# finalproject_2.net
KiCad netlist of a schematic drawn in EAGLE
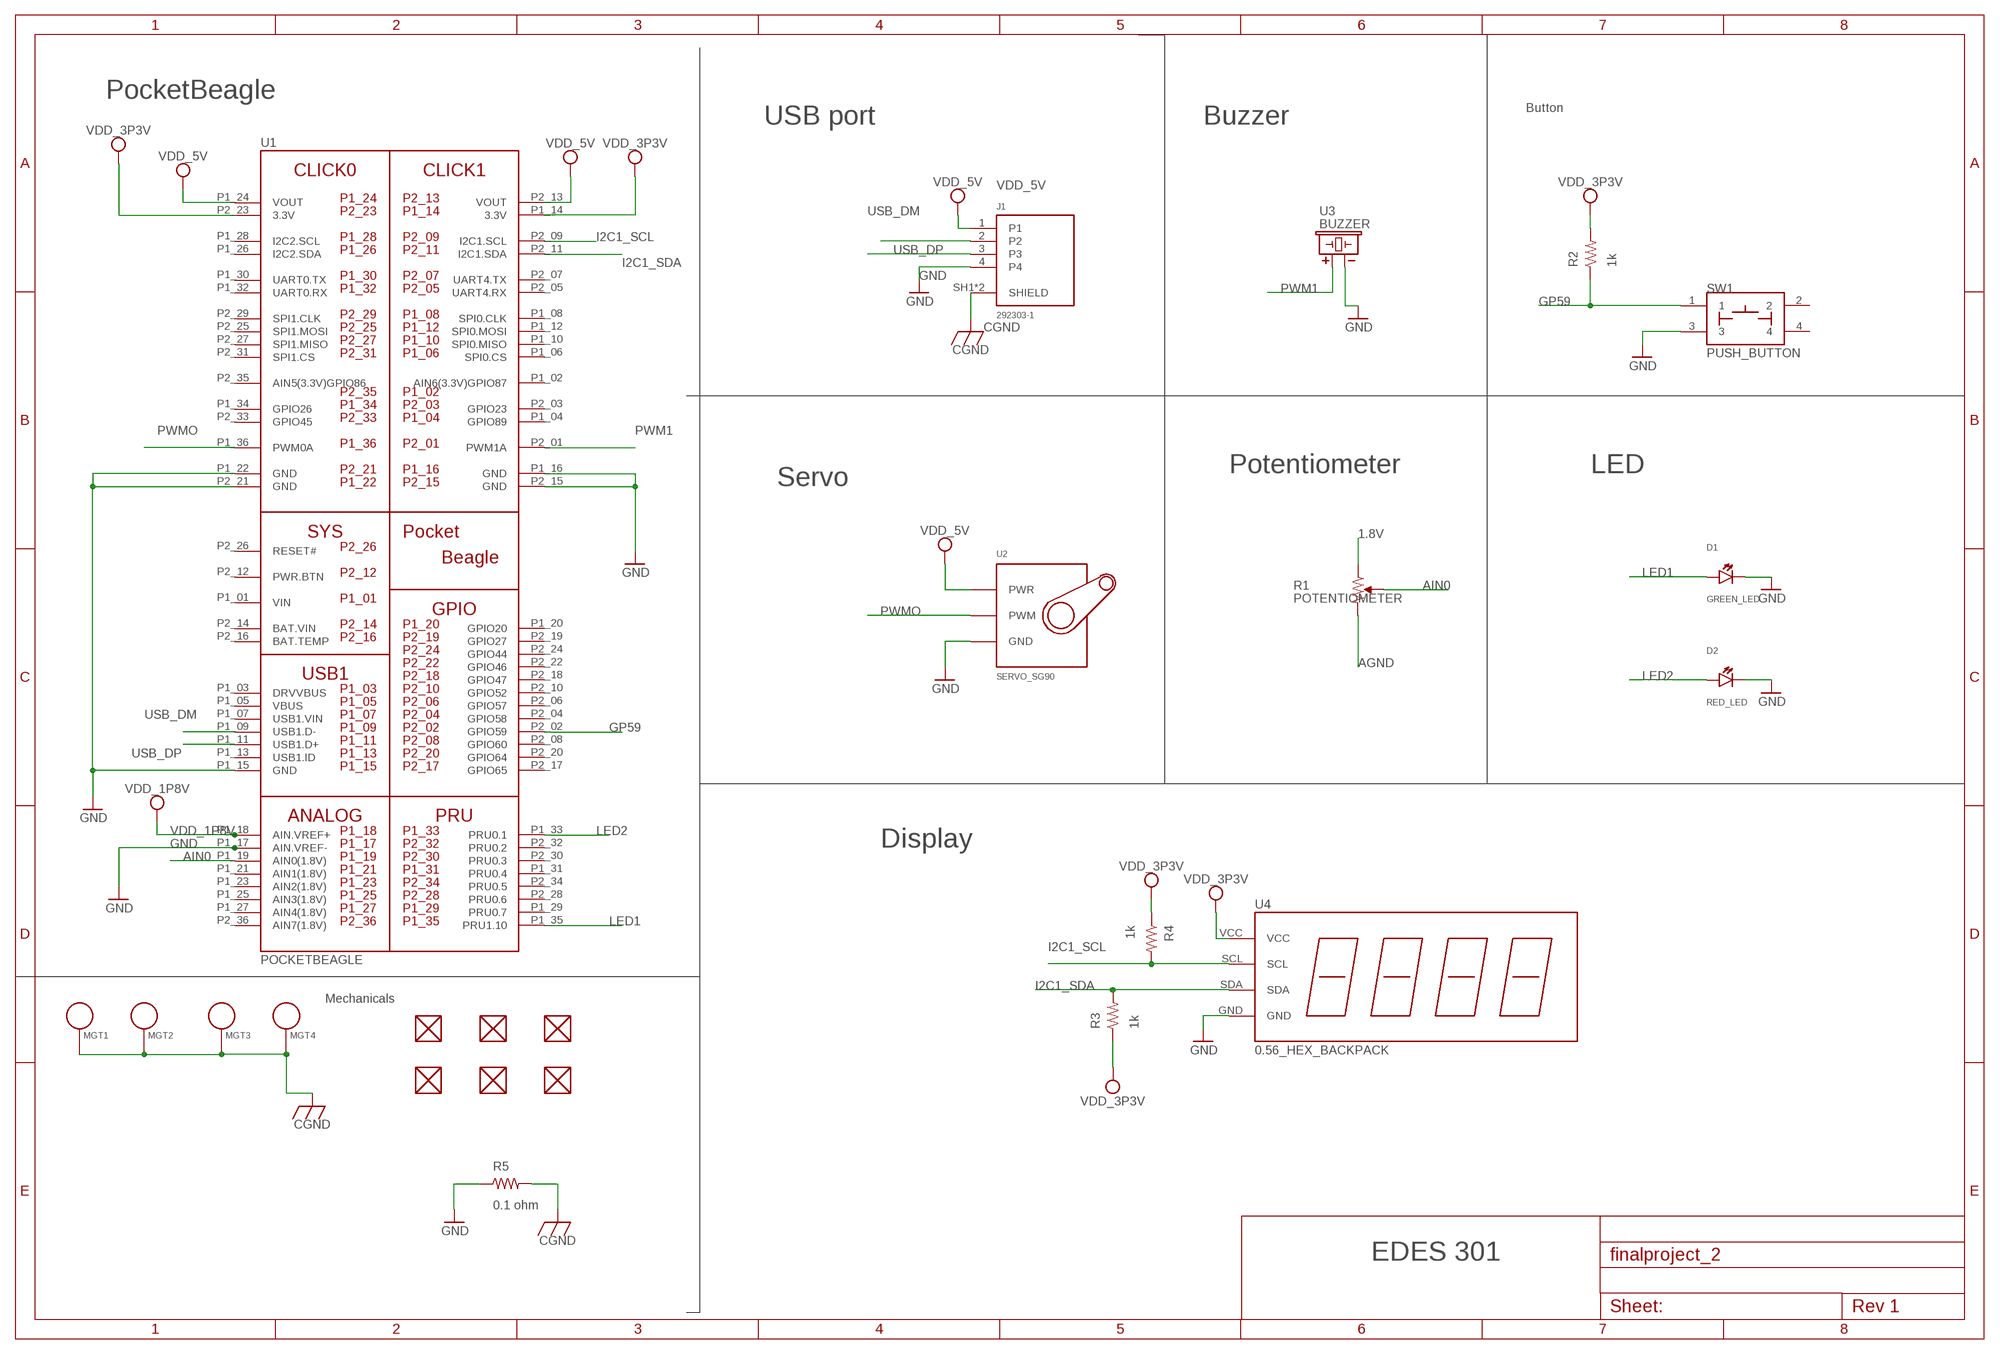
[diagram p0: schematic, sheet 1]

(export (version "E")
  (design (tool "Eeschema 10.0.6"))
  (components
    (comp (ref "D1")
      (value "GREEN_LED")
      (footprint "eagle-import:EIA-STD")
      (libsource (lib "eagle-import") (part "LED"))
    )
    (comp (ref "D2")
      (value "RED_LED")
      (footprint "eagle-import:EIA-STD")
      (libsource (lib "eagle-import") (part "LED"))
    )
    (comp (ref "FUD1")
      (value "FIDUCIAL")
      (footprint "eagle-import:FIDUCIAL_40MIL")
      (libsource (lib "eagle-import") (part "FIDUCIAL"))
    )
    (comp (ref "FUD2")
      (value "FIDUCIAL")
      (footprint "eagle-import:FIDUCIAL_40MIL")
      (libsource (lib "eagle-import") (part "FIDUCIAL"))
    )
    (comp (ref "FUD3")
      (value "FIDUCIAL")
      (footprint "eagle-import:FIDUCIAL_40MIL")
      (libsource (lib "eagle-import") (part "FIDUCIAL"))
    )
    (comp (ref "FUD4")
      (value "FIDUCIAL")
      (footprint "eagle-import:FIDUCIAL_40MIL")
      (libsource (lib "eagle-import") (part "FIDUCIAL"))
    )
    (comp (ref "FUD5")
      (value "FIDUCIAL")
      (footprint "eagle-import:FIDUCIAL_40MIL")
      (libsource (lib "eagle-import") (part "FIDUCIAL"))
    )
    (comp (ref "FUD6")
      (value "FIDUCIAL")
      (footprint "eagle-import:FIDUCIAL_40MIL")
      (libsource (lib "eagle-import") (part "FIDUCIAL"))
    )
    (comp (ref "J1")
      (value "292303-1")
      (footprint "eagle-import:TE_292303-1")
      (fields (field (name "MF") "TE Connectivity"))
      (libsource (lib "eagle-import") (part "292303-1"))
    )
    (comp (ref "MGT1")
      (value "MOUNTING_HOLE")
      (footprint "eagle-import:MOUNTING_HOLE")
      (libsource (lib "eagle-import") (part "MOUNTING_HOLE"))
    )
    (comp (ref "MGT2")
      (value "MOUNTING_HOLE")
      (footprint "eagle-import:MOUNTING_HOLE")
      (libsource (lib "eagle-import") (part "MOUNTING_HOLE"))
    )
    (comp (ref "MGT3")
      (value "MOUNTING_HOLE")
      (footprint "eagle-import:MOUNTING_HOLE")
      (libsource (lib "eagle-import") (part "MOUNTING_HOLE"))
    )
    (comp (ref "MGT4")
      (value "MOUNTING_HOLE")
      (footprint "eagle-import:MOUNTING_HOLE")
      (libsource (lib "eagle-import") (part "MOUNTING_HOLE"))
    )
    (comp (ref "R1")
      (value "POTENTIOMETER")
      (footprint "eagle-import:POT-PO90S")
      (libsource (lib "eagle-import") (part "POTENTIOMETER"))
    )
    (comp (ref "R2")
      (value "1k")
      (footprint "eagle-import:R0402")
      (libsource (lib "eagle-import") (part "R_R0402"))
    )
    (comp (ref "R3")
      (value "1k")
      (footprint "eagle-import:R0402")
      (libsource (lib "eagle-import") (part "R_R0402"))
    )
    (comp (ref "R4")
      (value "1k")
      (footprint "eagle-import:R0402")
      (libsource (lib "eagle-import") (part "R_R0402"))
    )
    (comp (ref "R5")
      (value "0.1 ohm")
      (footprint "eagle-import:R0805")
      (libsource (lib "eagle-import") (part "R_R0805"))
    )
    (comp (ref "SW1")
      (value "PUSH_BUTTON")
      (footprint "eagle-import:BUTTON_12.5MM")
      (libsource (lib "eagle-import") (part "PUSH_BUTTON"))
    )
    (comp (ref "U1")
      (value "POCKETBEAGLE")
      (footprint "eagle-import:POCKETBEAGLE")
      (libsource (lib "eagle-import") (part "POCKETBEAGLE"))
    )
    (comp (ref "U2")
      (value "SERVO_SG90")
      (footprint "eagle-import:SERVO-X1")
      (libsource (lib "eagle-import") (part "SERVO_SG90"))
    )
    (comp (ref "U3")
      (value "BUZZER")
      (footprint "eagle-import:BUZZER_6.5MM")
      (libsource (lib "eagle-import") (part "BUZZER"))
    )
    (comp (ref "U4")
      (value "0.56_HEX_BACKPACK")
      (footprint "eagle-import:0.56_HEX_BACKPACK")
      (libsource (lib "eagle-import") (part "0.56_HEX_BACKPACK"))
    )
  )
  (nets
    (net (code "1") (name "/1.8V") (class "Default")
      (node (ref "R1") (pin "CCW") (pinfunction "CCW_CCW") (pintype "passive"))
    )
    (net (code "2") (name "/AGND") (class "Default")
      (node (ref "R1") (pin "CW") (pinfunction "CW_CW") (pintype "passive"))
    )
    (net (code "3") (name "/AIN0") (class "Default")
      (node (ref "R1") (pin "S") (pinfunction "S_S") (pintype "bidirectional"))
      (node (ref "U1") (pin "P1_19") (pinfunction "AIN0(1.8V)_P1_19") (pintype "input"))
    )
    (net (code "4") (name "/BAT.VIN") (class "Default")
      (node (ref "U1") (pin "P2_14") (pinfunction "BAT.VIN_P2_14") (pintype "power_in"))
    )
    (net (code "5") (name "/GP59") (class "Default")
      (node (ref "R2") (pin "1") (pinfunction "1_1") (pintype "passive"))
      (node (ref "SW1") (pin "1") (pinfunction "1_1") (pintype "bidirectional"))
      (node (ref "U1") (pin "P2_02") (pinfunction "GPIO59_P2_02") (pintype "bidirectional"))
    )
    (net (code "6") (name "/I2C1_SCL") (class "Default")
      (node (ref "R4") (pin "2") (pinfunction "2_2") (pintype "passive"))
      (node (ref "U1") (pin "P2_09") (pinfunction "I2C1.SCL_P2_09") (pintype "bidirectional"))
      (node (ref "U4") (pin "SCL") (pinfunction "SCL_SCL") (pintype "bidirectional"))
    )
    (net (code "7") (name "/I2C1_SDA") (class "Default")
      (node (ref "R3") (pin "2") (pinfunction "2_2") (pintype "passive"))
      (node (ref "U1") (pin "P2_11") (pinfunction "I2C1.SDA_P2_11") (pintype "bidirectional"))
      (node (ref "U4") (pin "SDA") (pinfunction "SDA_SDA") (pintype "bidirectional"))
    )
    (net (code "8") (name "/LED1") (class "Default")
      (node (ref "D1") (pin "ANODE") (pinfunction "ANODE_ANODE") (pintype "bidirectional"))
      (node (ref "U1") (pin "P1_35") (pinfunction "PRU1.10_P1_35") (pintype "bidirectional"))
    )
    (net (code "9") (name "/LED2") (class "Default")
      (node (ref "D2") (pin "ANODE") (pinfunction "ANODE_ANODE") (pintype "bidirectional"))
      (node (ref "U1") (pin "P1_33") (pinfunction "PRU0.1_P1_33") (pintype "bidirectional"))
    )
    (net (code "10") (name "/PWM1") (class "Default")
      (node (ref "U1") (pin "P2_01") (pinfunction "PWM1A_P2_01") (pintype "bidirectional"))
      (node (ref "U3") (pin "+") (pinfunction "+_+") (pintype "passive"))
    )
    (net (code "11") (name "/PWMO") (class "Default")
      (node (ref "U1") (pin "P1_36") (pinfunction "PWM0A_P1_36") (pintype "bidirectional"))
      (node (ref "U2") (pin "SIG") (pinfunction "PWM_SIG") (pintype "bidirectional"))
    )
    (net (code "12") (name "/USB_DM") (class "Default")
      (node (ref "J1") (pin "2") (pinfunction "P2_2") (pintype "passive"))
      (node (ref "U1") (pin "P1_09") (pinfunction "USB1.D-_P1_09") (pintype "bidirectional"))
    )
    (net (code "13") (name "/USB_DP") (class "Default")
      (node (ref "J1") (pin "3") (pinfunction "P3_3") (pintype "passive"))
      (node (ref "U1") (pin "P1_11") (pinfunction "USB1.D+_P1_11") (pintype "bidirectional"))
    )
    (net (code "14") (name "/VIN") (class "Default")
      (node (ref "U1") (pin "P1_01") (pinfunction "VIN_P1_01") (pintype "power_in"))
    )
    (net (code "15") (name "CGND") (class "Default")
      (node (ref "J1") (pin "SH1") (pinfunction "SHIELD_SH1") (pintype "passive"))
      (node (ref "J1") (pin "SH2") (pinfunction "SHIELD_SH2") (pintype "passive"))
      (node (ref "MGT1") (pin "P$1") (pinfunction "P$1_P$1") (pintype "bidirectional"))
      (node (ref "MGT2") (pin "P$1") (pinfunction "P$1_P$1") (pintype "bidirectional"))
      (node (ref "MGT3") (pin "P$1") (pinfunction "P$1_P$1") (pintype "bidirectional"))
      (node (ref "MGT4") (pin "P$1") (pinfunction "P$1_P$1") (pintype "bidirectional"))
      (node (ref "R5") (pin "2") (pinfunction "2_2") (pintype "passive"))
    )
    (net (code "16") (name "GND") (class "Default")
      (node (ref "D1") (pin "CATHODE") (pinfunction "CATHODE_CATHODE") (pintype "bidirectional"))
      (node (ref "D2") (pin "CATHODE") (pinfunction "CATHODE_CATHODE") (pintype "bidirectional"))
      (node (ref "J1") (pin "4") (pinfunction "P4_4") (pintype "passive"))
      (node (ref "R5") (pin "1") (pinfunction "1_1") (pintype "passive"))
      (node (ref "SW1") (pin "3") (pinfunction "3_3") (pintype "bidirectional"))
      (node (ref "U1") (pin "P1_15") (pinfunction "GND_P1_15") (pintype "bidirectional"))
      (node (ref "U1") (pin "P1_16") (pinfunction "GND_P1_16") (pintype "power_in"))
      (node (ref "U1") (pin "P1_17") (pinfunction "AIN.VREF-_P1_17") (pintype "input"))
      (node (ref "U1") (pin "P1_22") (pinfunction "GND_P1_22") (pintype "power_in"))
      (node (ref "U1") (pin "P2_15") (pinfunction "GND_P2_15") (pintype "power_in"))
      (node (ref "U1") (pin "P2_21") (pinfunction "GND_P2_21") (pintype "power_in"))
      (node (ref "U2") (pin "GND") (pinfunction "GND_GND") (pintype "bidirectional"))
      (node (ref "U3") (pin "-") (pinfunction "-_-") (pintype "passive"))
      (node (ref "U4") (pin "GND") (pinfunction "GND_GND") (pintype "bidirectional"))
    )
    (net (code "17") (name "VDD_1P8V") (class "Default")
      (node (ref "U1") (pin "P1_18") (pinfunction "AIN.VREF+_P1_18") (pintype "input"))
    )
    (net (code "18") (name "VDD_3P3V") (class "Default")
      (node (ref "R2") (pin "2") (pinfunction "2_2") (pintype "passive"))
      (node (ref "R3") (pin "1") (pinfunction "1_1") (pintype "passive"))
      (node (ref "R4") (pin "1") (pinfunction "1_1") (pintype "passive"))
      (node (ref "U1") (pin "P1_14") (pinfunction "3.3V_P1_14") (pintype "power_in"))
      (node (ref "U1") (pin "P2_23") (pinfunction "3.3V_P2_23") (pintype "power_in"))
      (node (ref "U4") (pin "VCC") (pinfunction "VCC_VCC") (pintype "power_in"))
    )
    (net (code "19") (name "VDD_5V") (class "Default")
      (node (ref "J1") (pin "1") (pinfunction "P1_1") (pintype "passive"))
      (node (ref "U1") (pin "P1_24") (pinfunction "VOUT_P1_24") (pintype "power_in"))
      (node (ref "U1") (pin "P2_13") (pinfunction "VOUT_P2_13") (pintype "power_in"))
      (node (ref "U2") (pin "PWR") (pinfunction "PWR_PWR") (pintype "bidirectional"))
    )
    (net (code "20") (name "unconnected-(FUD1-PadP$1)") (class "Default")
      (node (ref "FUD1") (pin "P$1") (pinfunction "P$1_P$1") (pintype "no_connect"))
    )
    (net (code "21") (name "unconnected-(FUD2-PadP$1)") (class "Default")
      (node (ref "FUD2") (pin "P$1") (pinfunction "P$1_P$1") (pintype "no_connect"))
    )
    (net (code "22") (name "unconnected-(FUD3-PadP$1)") (class "Default")
      (node (ref "FUD3") (pin "P$1") (pinfunction "P$1_P$1") (pintype "no_connect"))
    )
    (net (code "23") (name "unconnected-(FUD4-PadP$1)") (class "Default")
      (node (ref "FUD4") (pin "P$1") (pinfunction "P$1_P$1") (pintype "no_connect"))
    )
    (net (code "24") (name "unconnected-(FUD5-PadP$1)") (class "Default")
      (node (ref "FUD5") (pin "P$1") (pinfunction "P$1_P$1") (pintype "no_connect"))
    )
    (net (code "25") (name "unconnected-(FUD6-PadP$1)") (class "Default")
      (node (ref "FUD6") (pin "P$1") (pinfunction "P$1_P$1") (pintype "no_connect"))
    )
    (net (code "26") (name "unconnected-(SW1-Pad2)") (class "Default")
      (node (ref "SW1") (pin "2") (pinfunction "2_2") (pintype "bidirectional"))
    )
    (net (code "27") (name "unconnected-(SW1-Pad4)") (class "Default")
      (node (ref "SW1") (pin "4") (pinfunction "4_4") (pintype "bidirectional"))
    )
    (net (code "28") (name "unconnected-(U1-AIN1(1.8V)-PadP1_21)") (class "Default")
      (node (ref "U1") (pin "P1_21") (pinfunction "AIN1(1.8V)_P1_21") (pintype "input"))
    )
    (net (code "29") (name "unconnected-(U1-AIN2(1.8V)-PadP1_23)") (class "Default")
      (node (ref "U1") (pin "P1_23") (pinfunction "AIN2(1.8V)_P1_23") (pintype "input"))
    )
    (net (code "30") (name "unconnected-(U1-AIN3(1.8V)-PadP1_25)") (class "Default")
      (node (ref "U1") (pin "P1_25") (pinfunction "AIN3(1.8V)_P1_25") (pintype "input"))
    )
    (net (code "31") (name "unconnected-(U1-AIN4(1.8V)-PadP1_27)") (class "Default")
      (node (ref "U1") (pin "P1_27") (pinfunction "AIN4(1.8V)_P1_27") (pintype "input"))
    )
    (net (code "32") (name "unconnected-(U1-AIN5(3.3V)GPIO86-PadP2_35)") (class "Default")
      (node (ref "U1") (pin "P2_35") (pinfunction "AIN5(3.3V)GPIO86_P2_35") (pintype "bidirectional"))
    )
    (net (code "33") (name "unconnected-(U1-AIN6(3.3V)GPIO87-PadP1_02)") (class "Default")
      (node (ref "U1") (pin "P1_02") (pinfunction "AIN6(3.3V)GPIO87_P1_02") (pintype "bidirectional"))
    )
    (net (code "34") (name "unconnected-(U1-AIN7(1.8V)-PadP2_36)") (class "Default")
      (node (ref "U1") (pin "P2_36") (pinfunction "AIN7(1.8V)_P2_36") (pintype "input"))
    )
    (net (code "35") (name "unconnected-(U1-BAT.TEMP-PadP2_16)") (class "Default")
      (node (ref "U1") (pin "P2_16") (pinfunction "BAT.TEMP_P2_16") (pintype "input"))
    )
    (net (code "36") (name "unconnected-(U1-DRVVBUS-PadP1_03)") (class "Default")
      (node (ref "U1") (pin "P1_03") (pinfunction "DRVVBUS_P1_03") (pintype "bidirectional"))
    )
    (net (code "37") (name "unconnected-(U1-GPIO20-PadP1_20)") (class "Default")
      (node (ref "U1") (pin "P1_20") (pinfunction "GPIO20_P1_20") (pintype "bidirectional"))
    )
    (net (code "38") (name "unconnected-(U1-GPIO23-PadP2_03)") (class "Default")
      (node (ref "U1") (pin "P2_03") (pinfunction "GPIO23_P2_03") (pintype "bidirectional"))
    )
    (net (code "39") (name "unconnected-(U1-GPIO26-PadP1_34)") (class "Default")
      (node (ref "U1") (pin "P1_34") (pinfunction "GPIO26_P1_34") (pintype "bidirectional"))
    )
    (net (code "40") (name "unconnected-(U1-GPIO27-PadP2_19)") (class "Default")
      (node (ref "U1") (pin "P2_19") (pinfunction "GPIO27_P2_19") (pintype "bidirectional"))
    )
    (net (code "41") (name "unconnected-(U1-GPIO44-PadP2_24)") (class "Default")
      (node (ref "U1") (pin "P2_24") (pinfunction "GPIO44_P2_24") (pintype "bidirectional"))
    )
    (net (code "42") (name "unconnected-(U1-GPIO45-PadP2_33)") (class "Default")
      (node (ref "U1") (pin "P2_33") (pinfunction "GPIO45_P2_33") (pintype "bidirectional"))
    )
    (net (code "43") (name "unconnected-(U1-GPIO46-PadP2_22)") (class "Default")
      (node (ref "U1") (pin "P2_22") (pinfunction "GPIO46_P2_22") (pintype "bidirectional"))
    )
    (net (code "44") (name "unconnected-(U1-GPIO47-PadP2_18)") (class "Default")
      (node (ref "U1") (pin "P2_18") (pinfunction "GPIO47_P2_18") (pintype "bidirectional"))
    )
    (net (code "45") (name "unconnected-(U1-GPIO52-PadP2_10)") (class "Default")
      (node (ref "U1") (pin "P2_10") (pinfunction "GPIO52_P2_10") (pintype "bidirectional"))
    )
    (net (code "46") (name "unconnected-(U1-GPIO57-PadP2_06)") (class "Default")
      (node (ref "U1") (pin "P2_06") (pinfunction "GPIO57_P2_06") (pintype "bidirectional"))
    )
    (net (code "47") (name "unconnected-(U1-GPIO58-PadP2_04)") (class "Default")
      (node (ref "U1") (pin "P2_04") (pinfunction "GPIO58_P2_04") (pintype "bidirectional"))
    )
    (net (code "48") (name "unconnected-(U1-GPIO60-PadP2_08)") (class "Default")
      (node (ref "U1") (pin "P2_08") (pinfunction "GPIO60_P2_08") (pintype "bidirectional"))
    )
    (net (code "49") (name "unconnected-(U1-GPIO64-PadP2_20)") (class "Default")
      (node (ref "U1") (pin "P2_20") (pinfunction "GPIO64_P2_20") (pintype "bidirectional"))
    )
    (net (code "50") (name "unconnected-(U1-GPIO65-PadP2_17)") (class "Default")
      (node (ref "U1") (pin "P2_17") (pinfunction "GPIO65_P2_17") (pintype "bidirectional"))
    )
    (net (code "51") (name "unconnected-(U1-GPIO89-PadP1_04)") (class "Default")
      (node (ref "U1") (pin "P1_04") (pinfunction "GPIO89_P1_04") (pintype "bidirectional"))
    )
    (net (code "52") (name "unconnected-(U1-I2C2.SCL-PadP1_28)") (class "Default")
      (node (ref "U1") (pin "P1_28") (pinfunction "I2C2.SCL_P1_28") (pintype "bidirectional"))
    )
    (net (code "53") (name "unconnected-(U1-I2C2.SDA-PadP1_26)") (class "Default")
      (node (ref "U1") (pin "P1_26") (pinfunction "I2C2.SDA_P1_26") (pintype "bidirectional"))
    )
    (net (code "54") (name "unconnected-(U1-PRU0.2-PadP2_32)") (class "Default")
      (node (ref "U1") (pin "P2_32") (pinfunction "PRU0.2_P2_32") (pintype "bidirectional"))
    )
    (net (code "55") (name "unconnected-(U1-PRU0.3-PadP2_30)") (class "Default")
      (node (ref "U1") (pin "P2_30") (pinfunction "PRU0.3_P2_30") (pintype "bidirectional"))
    )
    (net (code "56") (name "unconnected-(U1-PRU0.4-PadP1_31)") (class "Default")
      (node (ref "U1") (pin "P1_31") (pinfunction "PRU0.4_P1_31") (pintype "bidirectional"))
    )
    (net (code "57") (name "unconnected-(U1-PRU0.5-PadP2_34)") (class "Default")
      (node (ref "U1") (pin "P2_34") (pinfunction "PRU0.5_P2_34") (pintype "bidirectional"))
    )
    (net (code "58") (name "unconnected-(U1-PRU0.6-PadP2_28)") (class "Default")
      (node (ref "U1") (pin "P2_28") (pinfunction "PRU0.6_P2_28") (pintype "bidirectional"))
    )
    (net (code "59") (name "unconnected-(U1-PRU0.7-PadP1_29)") (class "Default")
      (node (ref "U1") (pin "P1_29") (pinfunction "PRU0.7_P1_29") (pintype "bidirectional"))
    )
    (net (code "60") (name "unconnected-(U1-PWR.BTN-PadP2_12)") (class "Default")
      (node (ref "U1") (pin "P2_12") (pinfunction "PWR.BTN_P2_12") (pintype "input"))
    )
    (net (code "61") (name "unconnected-(U1-RESET#-PadP2_26)") (class "Default")
      (node (ref "U1") (pin "P2_26") (pinfunction "RESET#_P2_26") (pintype "input"))
    )
    (net (code "62") (name "unconnected-(U1-SPI0.CLK-PadP1_08)") (class "Default")
      (node (ref "U1") (pin "P1_08") (pinfunction "SPI0.CLK_P1_08") (pintype "bidirectional"))
    )
    (net (code "63") (name "unconnected-(U1-SPI0.CS-PadP1_06)") (class "Default")
      (node (ref "U1") (pin "P1_06") (pinfunction "SPI0.CS_P1_06") (pintype "bidirectional"))
    )
    (net (code "64") (name "unconnected-(U1-SPI0.MISO-PadP1_10)") (class "Default")
      (node (ref "U1") (pin "P1_10") (pinfunction "SPI0.MISO_P1_10") (pintype "bidirectional"))
    )
    (net (code "65") (name "unconnected-(U1-SPI0.MOSI-PadP1_12)") (class "Default")
      (node (ref "U1") (pin "P1_12") (pinfunction "SPI0.MOSI_P1_12") (pintype "bidirectional"))
    )
    (net (code "66") (name "unconnected-(U1-SPI1.CLK-PadP2_29)") (class "Default")
      (node (ref "U1") (pin "P2_29") (pinfunction "SPI1.CLK_P2_29") (pintype "bidirectional"))
    )
    (net (code "67") (name "unconnected-(U1-SPI1.CS-PadP2_31)") (class "Default")
      (node (ref "U1") (pin "P2_31") (pinfunction "SPI1.CS_P2_31") (pintype "bidirectional"))
    )
    (net (code "68") (name "unconnected-(U1-SPI1.MISO-PadP2_27)") (class "Default")
      (node (ref "U1") (pin "P2_27") (pinfunction "SPI1.MISO_P2_27") (pintype "bidirectional"))
    )
    (net (code "69") (name "unconnected-(U1-SPI1.MOSI-PadP2_25)") (class "Default")
      (node (ref "U1") (pin "P2_25") (pinfunction "SPI1.MOSI_P2_25") (pintype "bidirectional"))
    )
    (net (code "70") (name "unconnected-(U1-UART0.RX-PadP1_32)") (class "Default")
      (node (ref "U1") (pin "P1_32") (pinfunction "UART0.RX_P1_32") (pintype "bidirectional"))
    )
    (net (code "71") (name "unconnected-(U1-UART0.TX-PadP1_30)") (class "Default")
      (node (ref "U1") (pin "P1_30") (pinfunction "UART0.TX_P1_30") (pintype "bidirectional"))
    )
    (net (code "72") (name "unconnected-(U1-UART4.RX-PadP2_05)") (class "Default")
      (node (ref "U1") (pin "P2_05") (pinfunction "UART4.RX_P2_05") (pintype "bidirectional"))
    )
    (net (code "73") (name "unconnected-(U1-UART4.TX-PadP2_07)") (class "Default")
      (node (ref "U1") (pin "P2_07") (pinfunction "UART4.TX_P2_07") (pintype "bidirectional"))
    )
    (net (code "74") (name "unconnected-(U1-USB1.ID-PadP1_13)") (class "Default")
      (node (ref "U1") (pin "P1_13") (pinfunction "USB1.ID_P1_13") (pintype "bidirectional"))
    )
    (net (code "75") (name "unconnected-(U1-USB1.VIN-PadP1_07)") (class "Default")
      (node (ref "U1") (pin "P1_07") (pinfunction "USB1.VIN_P1_07") (pintype "bidirectional"))
    )
    (net (code "76") (name "unconnected-(U1-VBUS-PadP1_05)") (class "Default")
      (node (ref "U1") (pin "P1_05") (pinfunction "VBUS_P1_05") (pintype "bidirectional"))
    )
  )
)
